# TIDA-01592_Power_Supply2.net
KiCad netlist of a schematic drawn in Altium Designer
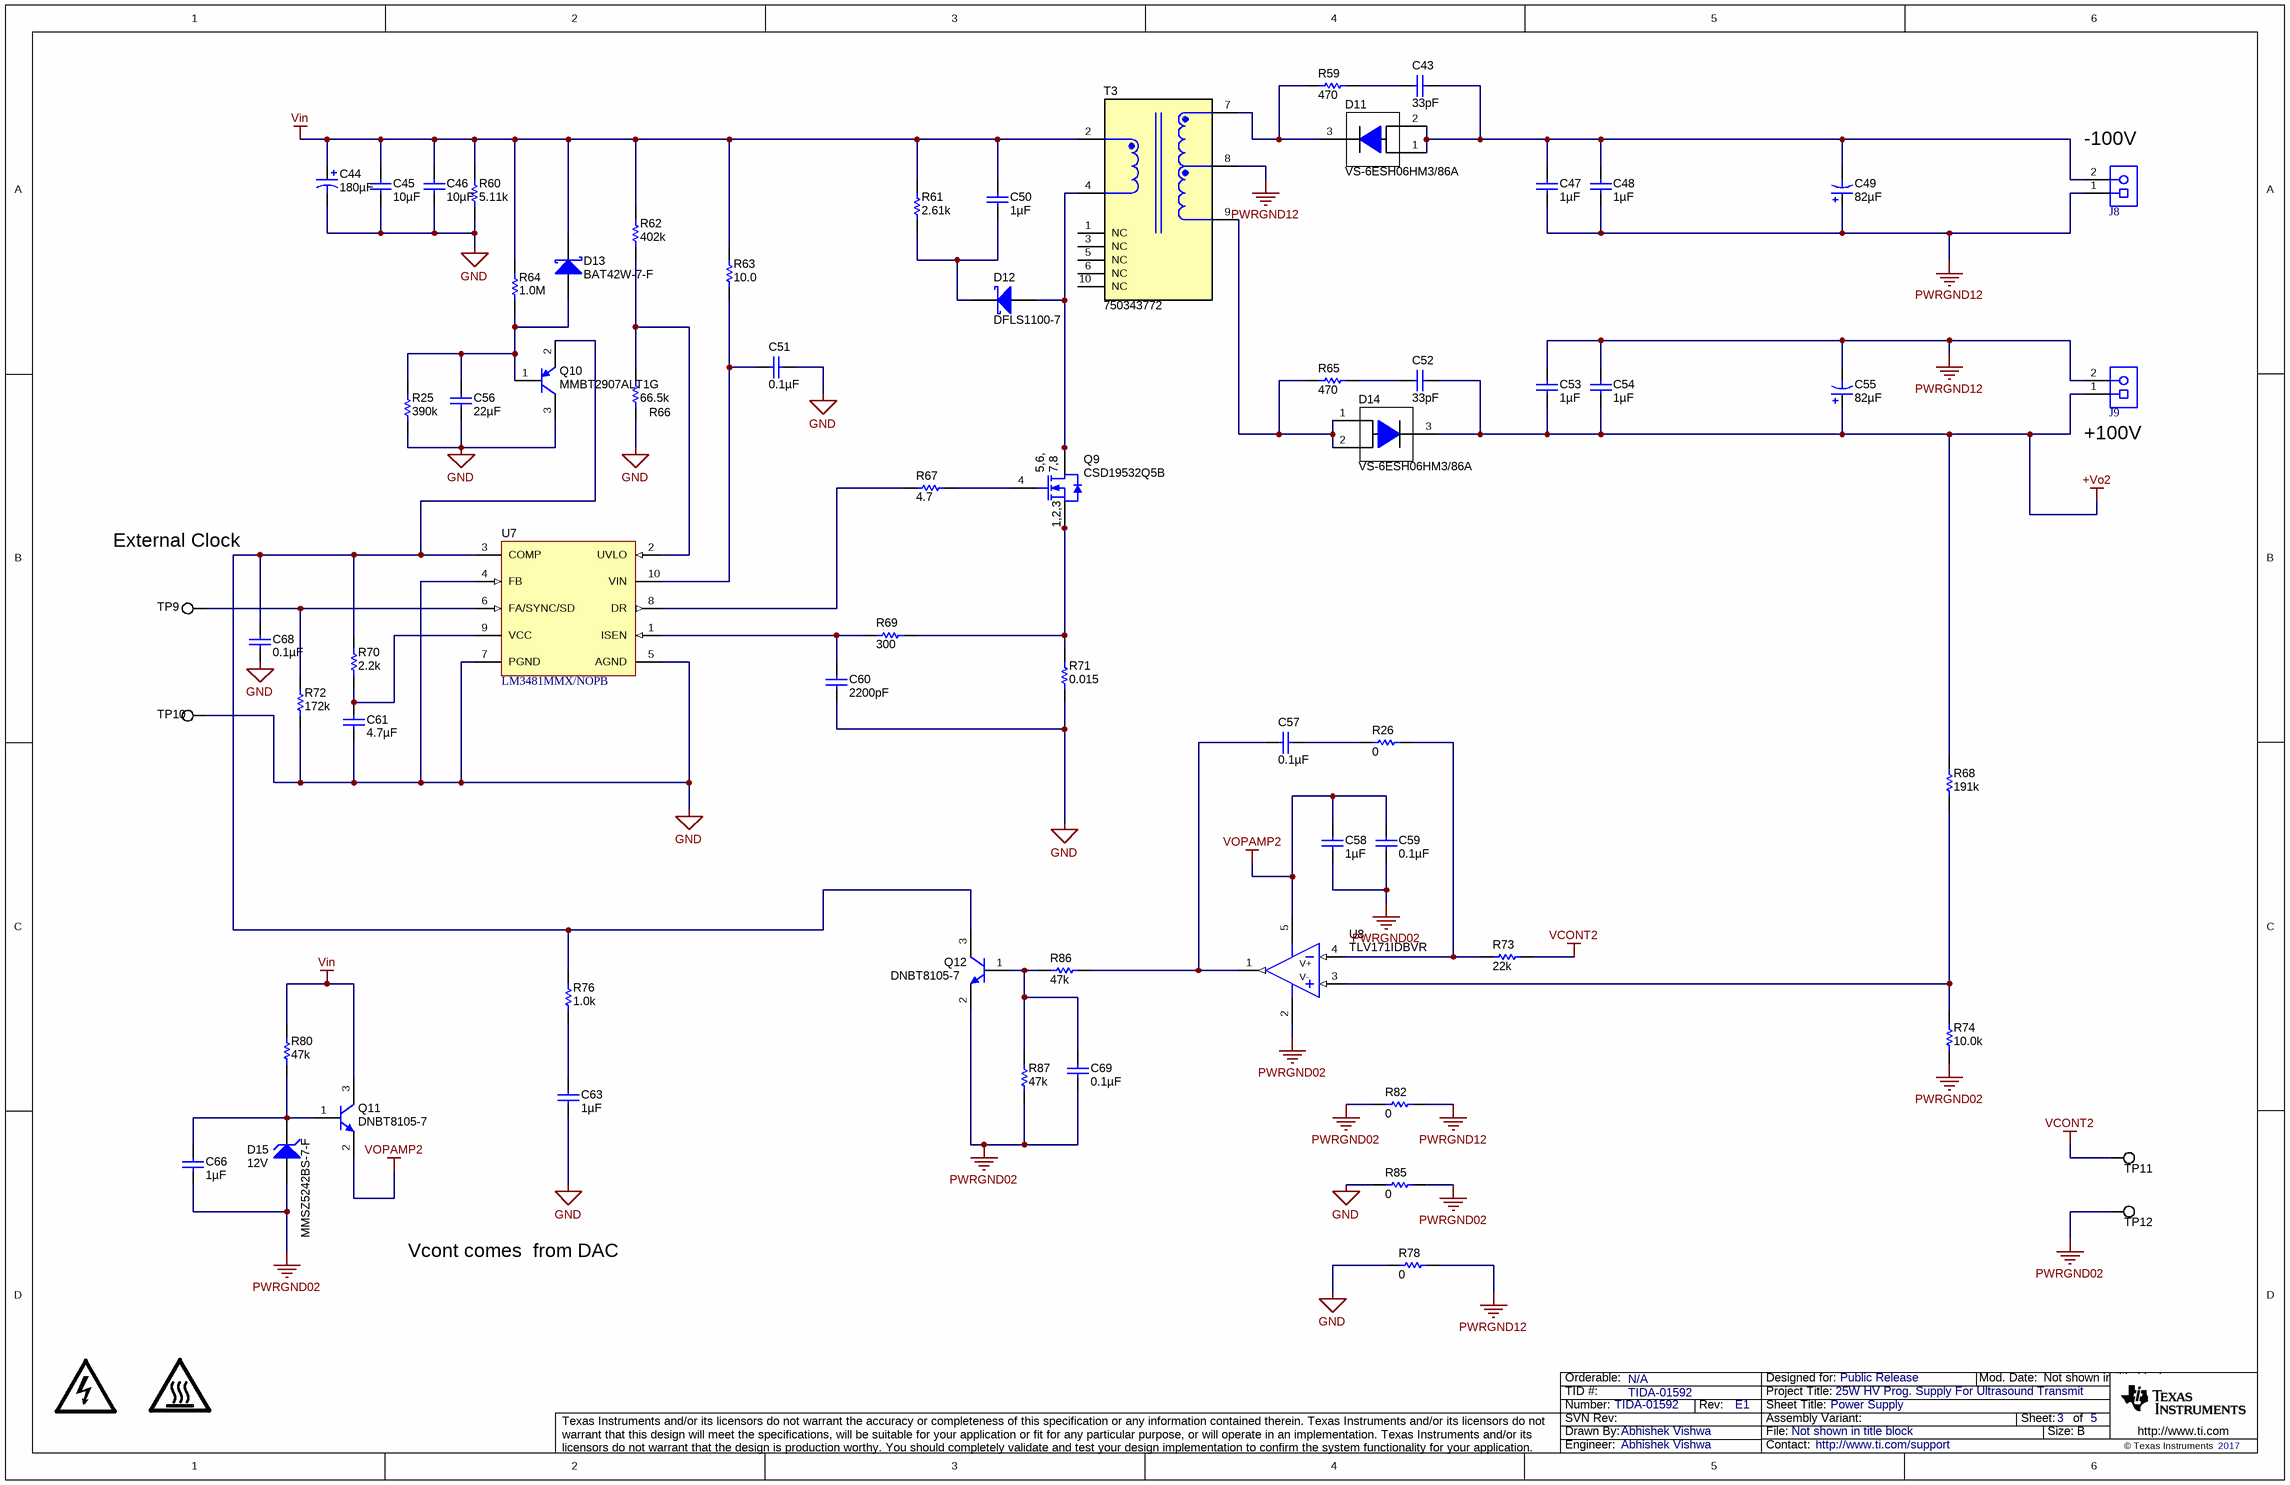
[diagram p0: TIDA-01592_Power Supply2.SchDoc]

(export (version "E")
  (design (tool "Eeschema 10.0.6"))
  (components
    (comp (ref "C43")
      (value "12067A330JAT2A")
      (footprint "1206")
      (description "CAP, CERM, 33 pF, 500 V,+/- 5%, C0G/NP0, 1206")
      (fields
        (field (name "VALUEDISPLAYED") "33pF")
        (field (name "MANUFACTURER") "AVX")
        (field (name "PUBLISHER") "Texas Instruments")
      )
      (libsource (lib "Capacitor_Ceramic") (part "12067A330JAT2A"))
    )
    (comp (ref "C44")
      (value "35TXW180MEFC6.3X25")
      (footprint "FC_630x1120")
      (description "CAP, AL, 180 µF, 35 V, +/- 20%, TH")
      (fields
        (field (name "VALUEDISPLAYED") "180µF")
        (field (name "MANUFACTURER") "Rubycon")
        (field (name "PUBLISHER") "Texas Instruments")
      )
      (libsource (lib "Capacitor_Aluminum") (part "EEU-FC1V470"))
    )
    (comp (ref "C45")
      (value "GRM31CR61H106KA12L")
      (footprint "1206_180")
      (description "CAP, CERM, 10 µF, 50 V,+/- 10%, X5R, 1206")
      (fields
        (field (name "VALUEDISPLAYED") "10µF")
        (field (name "MANUFACTURER") "MuRata")
        (field (name "PUBLISHER") "Texas Instruments")
      )
      (libsource (lib "Capacitor_Ceramic") (part "GRM31CR61H106KA12L"))
    )
    (comp (ref "C46")
      (value "GRM31CR61H106KA12L")
      (footprint "1206_180")
      (description "CAP, CERM, 10 µF, 50 V,+/- 10%, X5R, 1206")
      (fields
        (field (name "VALUEDISPLAYED") "10µF")
        (field (name "MANUFACTURER") "MuRata")
        (field (name "PUBLISHER") "Texas Instruments")
      )
      (libsource (lib "Capacitor_Ceramic") (part "GRM31CR61H106KA12L"))
    )
    (comp (ref "C47")
      (value "C4532X7T2E105M250KE")
      (footprint "1812_180")
      (description "CAP, CERM, 1 µF, 250 V,+/- 20%, X7T, 1812")
      (fields
        (field (name "VALUEDISPLAYED") "1µF")
        (field (name "MANUFACTURER") "TDK Corporation")
        (field (name "PUBLISHER") "Texas Instruments")
      )
      (libsource (lib "Capacitor_Ceramic") (part "C4532X7R1H105K160KA"))
    )
    (comp (ref "C48")
      (value "C4532X7T2E105M250KE")
      (footprint "1812_180")
      (description "CAP, CERM, 1 µF, 250 V,+/- 20%, X7T, 1812")
      (fields
        (field (name "VALUEDISPLAYED") "1µF")
        (field (name "MANUFACTURER") "TDK Corporation")
        (field (name "PUBLISHER") "Texas Instruments")
      )
      (libsource (lib "Capacitor_Ceramic") (part "C4532X7R1H105K160KA"))
    )
    (comp (ref "C49")
      (value "UCY2C820MPD9")
      (footprint "NHG_1000x2000")
      (description "CAP, AL, 82 µF, 160 V, +/- 20%, TH")
      (fields
        (field (name "VALUEDISPLAYED") "82µF")
        (field (name "MANUFACTURER") "Nichicon")
        (field (name "PUBLISHER") "Texas Instruments")
      )
      (libsource (lib "Capacitor_Aluminum") (part "ECA-2AHG101"))
    )
    (comp (ref "C50")
      (value "GRM31CR72A105KA01L")
      (footprint "1206_180")
      (description "CAP, CERM, 1 µF, 100 V,+/- 10%, X7R, 1206")
      (fields
        (field (name "VALUEDISPLAYED") "1µF")
        (field (name "MANUFACTURER") "MuRata")
        (field (name "PUBLISHER") "Texas Instruments")
      )
      (libsource (lib "Capacitor_Ceramic") (part "GRM31CR72A105KA01L"))
    )
    (comp (ref "C51")
      (value "GRM188R71H104KA93D")
      (footprint "0603")
      (description "CAP, CERM, 0.1 µF, 50 V,+/- 10%, X7R, 0603")
      (fields
        (field (name "VALUEDISPLAYED") "0.1µF")
        (field (name "MANUFACTURER") "MuRata")
        (field (name "PUBLISHER") "Texas Instruments")
      )
      (libsource (lib "Capacitor_Ceramic") (part "GRM188R71H104KA93D"))
    )
    (comp (ref "C52")
      (value "12067A330JAT2A")
      (footprint "1206")
      (description "CAP, CERM, 33 pF, 500 V,+/- 5%, C0G/NP0, 1206")
      (fields
        (field (name "VALUEDISPLAYED") "33pF")
        (field (name "MANUFACTURER") "AVX")
        (field (name "PUBLISHER") "Texas Instruments")
      )
      (libsource (lib "Capacitor_Ceramic") (part "12067A330JAT2A"))
    )
    (comp (ref "C53")
      (value "C4532X7T2E105M250KE")
      (footprint "1812_180")
      (description "CAP, CERM, 1 µF, 250 V,+/- 20%, X7T, 1812")
      (fields
        (field (name "VALUEDISPLAYED") "1µF")
        (field (name "MANUFACTURER") "TDK Corporation")
        (field (name "PUBLISHER") "Texas Instruments")
      )
      (libsource (lib "Capacitor_Ceramic") (part "C4532X7R1H105K160KA"))
    )
    (comp (ref "C54")
      (value "C4532X7T2E105M250KE")
      (footprint "1812_180")
      (description "CAP, CERM, 1 µF, 250 V,+/- 20%, X7T, 1812")
      (fields
        (field (name "VALUEDISPLAYED") "1µF")
        (field (name "MANUFACTURER") "TDK Corporation")
        (field (name "PUBLISHER") "Texas Instruments")
      )
      (libsource (lib "Capacitor_Ceramic") (part "C4532X7R1H105K160KA"))
    )
    (comp (ref "C55")
      (value "UCY2C820MPD9")
      (footprint "NHG_1000x2000")
      (description "CAP, AL, 82 µF, 160 V, +/- 20%, TH")
      (fields
        (field (name "VALUEDISPLAYED") "82µF")
        (field (name "MANUFACTURER") "Nichicon")
        (field (name "PUBLISHER") "Texas Instruments")
      )
      (libsource (lib "Capacitor_Aluminum") (part "ECA-2AHG101"))
    )
    (comp (ref "C56")
      (value "C2012X5R1V226M125AC")
      (footprint "0805_HV1")
      (description "CAP, CERM, 22 µF, 35 V,+/- 20%, X5R, 0805")
      (fields
        (field (name "VALUEDISPLAYED") "22µF")
        (field (name "MANUFACTURER") "TDK Corporation")
        (field (name "PUBLISHER") "Texas Instruments")
      )
      (libsource (lib "Capacitor_Ceramic") (part "GRM21BC81C226ME44L"))
    )
    (comp (ref "C57")
      (value "GRM188R71H104KA93D")
      (footprint "0603")
      (description "CAP, CERM, 0.1 µF, 50 V,+/- 10%, X7R, 0603")
      (fields
        (field (name "VALUEDISPLAYED") "0.1µF")
        (field (name "MANUFACTURER") "MuRata")
        (field (name "PUBLISHER") "Texas Instruments")
      )
      (libsource (lib "Capacitor_Ceramic") (part "GRM188R71H104KA93D"))
    )
    (comp (ref "C58")
      (value "UMK107AB7105KA-T")
      (footprint "0603")
      (description "CAP, CERM, 1 µF, 50 V,+/- 10%, X7R, 0603")
      (fields
        (field (name "VALUEDISPLAYED") "1µF")
        (field (name "MANUFACTURER") "Taiyo Yuden")
        (field (name "PUBLISHER") "Texas Instruments")
      )
      (libsource (lib "Capacitor_Ceramic") (part "UMK107AB7105KA-T"))
    )
    (comp (ref "C59")
      (value "GRM188R71H104KA93D")
      (footprint "0603")
      (description "CAP, CERM, 0.1 µF, 50 V,+/- 10%, X7R, 0603")
      (fields
        (field (name "VALUEDISPLAYED") "0.1µF")
        (field (name "MANUFACTURER") "MuRata")
        (field (name "PUBLISHER") "Texas Instruments")
      )
      (libsource (lib "Capacitor_Ceramic") (part "GRM188R71H104KA93D"))
    )
    (comp (ref "C60")
      (value "GRM155R61H222KA01D")
      (footprint "0402")
      (description "CAP, CERM, 2200 pF, 50 V,+/- 10%, X5R, 0402")
      (fields
        (field (name "VALUEDISPLAYED") "2200pF")
        (field (name "MANUFACTURER") "MuRata")
        (field (name "PUBLISHER") "Texas Instruments")
      )
      (libsource (lib "Capacitor_Ceramic") (part "GRM155R61H222KA01D"))
    )
    (comp (ref "C61")
      (value "0603ZD475KAT2A")
      (footprint "0603")
      (description "CAP, CERM, 4.7 µF, 10 V,+/- 10%, X5R, 0603")
      (fields
        (field (name "VALUEDISPLAYED") "4.7µF")
        (field (name "MANUFACTURER") "AVX")
        (field (name "PUBLISHER") "Texas Instruments")
      )
      (libsource (lib "Capacitor_Ceramic") (part "0603ZD475KAT2A"))
    )
    (comp (ref "C63")
      (value "C0603C105K3RACTU")
      (footprint "0603")
      (description "CAP, CERM, 1 µF, 25 V,+/- 10%, X7R, 0603")
      (fields
        (field (name "VALUEDISPLAYED") "1µF")
        (field (name "MANUFACTURER") "Kemet")
        (field (name "PUBLISHER") "Texas Instruments")
      )
      (libsource (lib "Capacitor_Ceramic") (part "C0603C105K3RACTU"))
    )
    (comp (ref "C66")
      (value "C0603C105K3RACTU")
      (footprint "0603")
      (description "CAP, CERM, 1 µF, 25 V,+/- 10%, X7R, 0603")
      (fields
        (field (name "VALUEDISPLAYED") "1µF")
        (field (name "MANUFACTURER") "Kemet")
        (field (name "PUBLISHER") "Texas Instruments")
      )
      (libsource (lib "Capacitor_Ceramic") (part "C0603C105K3RACTU"))
    )
    (comp (ref "C68")
      (value "GRM188R71H104KA93D")
      (footprint "0603")
      (description "CAP, CERM, 0.1 µF, 50 V,+/- 10%, X7R, 0603")
      (fields
        (field (name "VALUEDISPLAYED") "0.1µF")
        (field (name "MANUFACTURER") "MuRata")
        (field (name "PUBLISHER") "Texas Instruments")
      )
      (libsource (lib "Capacitor_Ceramic") (part "GRM188R71H104KA93D"))
    )
    (comp (ref "C69")
      (value "GRM188R71H104KA93D")
      (footprint "0603")
      (description "CAP, CERM, 0.1 µF, 50 V,+/- 10%, X7R, 0603")
      (fields
        (field (name "VALUEDISPLAYED") "0.1µF")
        (field (name "MANUFACTURER") "MuRata")
        (field (name "PUBLISHER") "Texas Instruments")
      )
      (libsource (lib "Capacitor_Ceramic") (part "GRM188R71H104KA93D"))
    )
    (comp (ref "D11")
      (value "VS-6ESH06HM3/86A")
      (footprint "TO-277A")
      (description "Diode, Hyperfast, 600 V, 6 A, AEC-Q101, TO-277A")
      (fields
        (field (name "MANUFACTURER") "Vishay-Semiconductor")
        (field (name "SYMBOLCREATOR") "a0412235")
        (field (name "PUBLISHER") "Texas Instruments")
      )
      (libsource (lib "Diode") (part "VS-6ESH06HM3/86A"))
    )
    (comp (ref "D12")
      (value "DFLS1100-7")
      (footprint "PowerDI123")
      (description "Diode, Schottky, 100 V, 1 A, PowerDI123")
      (fields (field (name "MANUFACTURER") "Diodes Inc.") (field (name "PUBLISHER") "Texas Instruments"))
      (libsource (lib "Diode") (part "DFLS1100-7"))
    )
    (comp (ref "D13")
      (value "BAT42W-7-F")
      (footprint "SOD-123")
      (description "Diode, Schottky, 30 V, 0.2 A, SOD-123")
      (fields (field (name "MANUFACTURER") "Diodes Inc.") (field (name "PUBLISHER") "Texas Instruments"))
      (libsource (lib "Diode") (part "BAT42W-7-F"))
    )
    (comp (ref "D14")
      (value "VS-6ESH06HM3/86A")
      (footprint "TO-277A")
      (description "Diode, Hyperfast, 600 V, 6 A, AEC-Q101, TO-277A")
      (fields
        (field (name "MANUFACTURER") "Vishay-Semiconductor")
        (field (name "SYMBOLCREATOR") "a0412235")
        (field (name "PUBLISHER") "Texas Instruments")
      )
      (libsource (lib "") (part "VS-6ESH06HM3/86A_1"))
    )
    (comp (ref "D15")
      (value "MMSZ5242BS-7-F")
      (footprint "SOD-323")
      (description "Diode, Zener, 12 V, 200 mW, SOD-323")
      (fields
        (field (name "ALTIUM_VALUE") "12V")
        (field (name "MANUFACTURER") "Diodes Inc.")
        (field (name "SYMBOLCREATOR") "a0412235")
        (field (name "PUBLISHER") "Texas Instruments")
      )
      (libsource (lib "ZenerDiodes") (part "MMSZ5242BS-7-F"))
    )
    (comp (ref "J8")
      (value "1727010")
      (footprint "PhoenixConact_1727010")
      (description "Conn Term Block, 2POS, 3.81mm, TH")
      (fields
        (field (name "MANUFACTURER") "Phoenix Contact")
        (field (name "SYMBOLCREATOR") "a0412235")
        (field (name "PUBLISHER") "Texas Instruments")
      )
      (libsource (lib "Connectors_Phoenix_Contact") (part "1727010"))
    )
    (comp (ref "J9")
      (value "1727010")
      (footprint "PhoenixConact_1727010")
      (description "Conn Term Block, 2POS, 3.81mm, TH")
      (fields
        (field (name "MANUFACTURER") "Phoenix Contact")
        (field (name "SYMBOLCREATOR") "a0412235")
        (field (name "PUBLISHER") "Texas Instruments")
      )
      (libsource (lib "Connectors_Phoenix_Contact") (part "1727010"))
    )
    (comp (ref "Q9")
      (value "CSD19532Q5B")
      (footprint "DNK0008A")
      (description "MOSFET, N-CH, 100 V, 17 A, DNK0008A (VSON-CLIP-8)")
      (fields
        (field (name "MANUFACTURER") "Texas Instruments")
        (field (name "PUBLISHER") "Texas Instruments")
      )
      (libsource (lib "FETs") (part "CSD19532Q5B"))
    )
    (comp (ref "Q10")
      (value "MMBT2907ALT1G")
      (footprint "SOT-23")
      (description "Transistor, PNP, 60 V, 0.6 A, SOT-23")
      (fields (field (name "MANUFACTURER") "ON Semiconductor") (field (name "PUBLISHER") "Texas Instruments"))
      (libsource (lib "Bipolar_Transistor") (part "MMBT2907ALT1G, ON Semiconductor"))
    )
    (comp (ref "Q11")
      (value "DNBT8105-7")
      (footprint "SOT-23")
      (description "Transistor, NPN, 60 V, 1 A, AEC-Q101, SOT-23")
      (fields (field (name "MANUFACTURER") "Diodes Inc.") (field (name "PUBLISHER") "Texas Instruments"))
      (libsource (lib "Bipolar_Transistor") (part "DNBT8105-7, Diodes Inc."))
    )
    (comp (ref "Q12")
      (value "DNBT8105-7")
      (footprint "SOT-23")
      (description "Transistor, NPN, 60 V, 1 A, AEC-Q101, SOT-23")
      (fields (field (name "MANUFACTURER") "Diodes Inc.") (field (name "PUBLISHER") "Texas Instruments"))
      (libsource (lib "Bipolar_Transistor") (part "DNBT8105-7, Diodes Inc."))
    )
    (comp (ref "R25")
      (value "CRCW0603390KJNEA")
      (footprint "0603")
      (description "RES, 390 k, 5%, 0.1 W, 0603")
      (fields
        (field (name "VALUEDISPLAYED") "390k")
        (field (name "MANUFACTURER") "Vishay-Dale")
        (field (name "PUBLISHER") "Texas Instruments")
      )
      (libsource (lib "Resistor_0603") (part "CRCW0603390KJNEA"))
    )
    (comp (ref "R26")
      (value "CRCW04020000Z0ED")
      (footprint "0402")
      (description "RES, 0, 5%, 0.063 W, 0402")
      (fields
        (field (name "VALUEDISPLAYED") "0")
        (field (name "MANUFACTURER") "Vishay-Dale")
        (field (name "PUBLISHER") "Texas Instruments")
      )
      (libsource (lib "Resistor_0402") (part "CRCW04020000Z0ED"))
    )
    (comp (ref "R59")
      (value "CRCW1206470RJNEA")
      (footprint "1206")
      (description "RES, 470, 5%, 0.25 W, 1206")
      (fields
        (field (name "VALUEDISPLAYED") "470")
        (field (name "MANUFACTURER") "Vishay-Dale")
        (field (name "PUBLISHER") "Texas Instruments")
      )
      (libsource (lib "Resistor_1206") (part "CRCW1206470RJNEA"))
    )
    (comp (ref "R60")
      (value "TNPW06035K11BEEA")
      (footprint "TNPW0603")
      (description "RES, 5.11 k, 0.1%, 0.1 W, AEC-Q200 Grade 1, 0603")
      (fields
        (field (name "VALUEDISPLAYED") "5.11k")
        (field (name "MANUFACTURER") "Vishay-Dale")
        (field (name "PUBLISHER") "Texas Instruments")
      )
      (libsource (lib "Resistor_0603") (part "TNPW06035K11BEEA"))
    )
    (comp (ref "R61")
      (value "CRCW20102K61FKEF")
      (footprint "2010")
      (description "RES, 2.61 k, 1%, 0.75 W, AEC-Q200 Grade 0, 2010")
      (fields
        (field (name "VALUEDISPLAYED") "2.61k")
        (field (name "MANUFACTURER") "Vishay-Dale")
        (field (name "PUBLISHER") "Texas Instruments")
      )
      (libsource (lib "Resistor_2010") (part "CRCW20102K61FKEF"))
    )
    (comp (ref "R62")
      (value "CRCW0603402KFKEA")
      (footprint "0603")
      (description "RES, 402 k, 1%, 0.1 W, 0603")
      (fields
        (field (name "VALUEDISPLAYED") "402k")
        (field (name "MANUFACTURER") "Vishay-Dale")
        (field (name "PUBLISHER") "Texas Instruments")
      )
      (libsource (lib "Resistor_0603") (part "CRCW0603402KFKEA"))
    )
    (comp (ref "R63")
      (value "CRCW060310R0FKEAHP")
      (footprint "0603")
      (description "RES, 10.0, 1%, 0.25 W, 0603")
      (fields
        (field (name "R4") "10.0")
        (field (name "MANUFACTURER") "Vishay-Dale")
        (field (name "PUBLISHER") "Texas Instruments")
      )
      (libsource (lib "Resistor_0603") (part "CRCW060310R0FKEAHP"))
    )
    (comp (ref "R64")
      (value "CRCW06031M00JNEA")
      (footprint "0603")
      (description "RES, 1.0 M, 5%, 0.1 W, 0603")
      (fields
        (field (name "VALUEDISPLAYED") "1.0M")
        (field (name "MANUFACTURER") "Vishay-Dale")
        (field (name "PUBLISHER") "Texas Instruments")
      )
      (libsource (lib "Resistor_0603") (part "CRCW06031M00JNEA"))
    )
    (comp (ref "R65")
      (value "CRCW1206470RJNEA")
      (footprint "1206")
      (description "RES, 470, 5%, 0.25 W, 1206")
      (fields
        (field (name "VALUEDISPLAYED") "470")
        (field (name "MANUFACTURER") "Vishay-Dale")
        (field (name "PUBLISHER") "Texas Instruments")
      )
      (libsource (lib "Resistor_1206") (part "CRCW1206470RJNEA"))
    )
    (comp (ref "R66")
      (value "CRCW060366K5FKEA")
      (footprint "0603")
      (description "RES, 66.5 k, 1%, 0.1 W, 0603")
      (fields
        (field (name "VALUEDISPLAYED") "66.5k")
        (field (name "MANUFACTURER") "Vishay-Dale")
        (field (name "PUBLISHER") "Texas Instruments")
      )
      (libsource (lib "Resistor_0603") (part "CRCW060366K5FKEA"))
    )
    (comp (ref "R67")
      (value "CRCW06034R70JNEA")
      (footprint "0603")
      (description "RES, 4.7, 5%, 0.1 W, 0603")
      (fields
        (field (name "VALUEDISPLAYED") "4.7")
        (field (name "MANUFACTURER") "Vishay-Dale")
        (field (name "PUBLISHER") "Texas Instruments")
      )
      (libsource (lib "Resistor_0603") (part "CRCW06034R70JNEA"))
    )
    (comp (ref "R68")
      (value "CRCW0603191KFKEA")
      (footprint "0603")
      (description "RES, 191 k, 1%, 0.1 W, 0603")
      (fields
        (field (name "VALUEDISPLAYED") "191k")
        (field (name "MANUFACTURER") "Vishay-Dale")
        (field (name "PUBLISHER") "Texas Instruments")
      )
      (libsource (lib "Resistor_0603") (part "CRCW0603191KFKEA"))
    )
    (comp (ref "R69")
      (value "CRCW0603300RJNEA")
      (footprint "0603")
      (description "RES, 300, 5%, 0.1 W, 0603")
      (fields
        (field (name "VALUEDISPLAYED") "300")
        (field (name "MANUFACTURER") "Vishay-Dale")
        (field (name "PUBLISHER") "Texas Instruments")
      )
      (libsource (lib "Resistor_0603") (part "CRCW0603300RJNEA"))
    )
    (comp (ref "R70")
      (value "ERJ-3GEYJ222V")
      (footprint "0603")
      (description "RES, 2.2 k, 5%, 0.1 W, AEC-Q200 Grade 0, 0603")
      (fields
        (field (name "VALUEDISPLAYED") "2.2k")
        (field (name "MANUFACTURER") "Panasonic")
        (field (name "PUBLISHER") "Texas Instruments")
      )
      (libsource (lib "Resistor_0603") (part "ERJ-3GEYJ222V"))
    )
    (comp (ref "R71")
      (value "WSL2010R0150FEA18")
      (footprint "2010")
      (description "RES, 0.015, 1%, 1 W, 2010")
      (fields
        (field (name "VALUEDISPLAYED") "0.015")
        (field (name "MANUFACTURER") "Vishay-Dale")
        (field (name "PUBLISHER") "Texas Instruments")
      )
      (libsource (lib "Resistor_2010") (part "WSL2010R0150FEA18"))
    )
    (comp (ref "R72")
      (value "RT0603DRE07172KL")
      (footprint "0603")
      (description "RES, 172 k, 0.5%, 0.1 W, 0603")
      (fields
        (field (name "VALUEDISPLAYED") "172k")
        (field (name "MANUFACTURER") "Yageo America")
        (field (name "PUBLISHER") "Texas Instruments")
      )
      (libsource (lib "Resistor_0603") (part "RT0603DRE07172KL"))
    )
    (comp (ref "R73")
      (value "CRCW060322K0JNEA")
      (footprint "0603")
      (description "RES, 22 k, 5%, 0.1 W, 0603")
      (fields
        (field (name "VALUEDISPLAYED") "22k")
        (field (name "MANUFACTURER") "Vishay-Dale")
        (field (name "PUBLISHER") "Texas Instruments")
      )
      (libsource (lib "Resistor_0603") (part "CRCW060322K0JNEA"))
    )
    (comp (ref "R74")
      (value "CRCW060310K0FKEA")
      (footprint "0603")
      (description "RES, 10.0 k, 1%, 0.1 W, 0603")
      (fields
        (field (name "VALUEDISPLAYED") "10.0k")
        (field (name "MANUFACTURER") "Vishay-Dale")
        (field (name "PUBLISHER") "Texas Instruments")
      )
      (libsource (lib "Resistor_0603") (part "CRCW060310K0FKEA"))
    )
    (comp (ref "R76")
      (value "CRCW06031K00JNEA")
      (footprint "0603")
      (description "RES, 1.0 k, 5%, 0.1 W, 0603")
      (fields
        (field (name "VALUEDISPLAYED") "1.0k")
        (field (name "MANUFACTURER") "Vishay-Dale")
        (field (name "PUBLISHER") "Texas Instruments")
      )
      (libsource (lib "Resistor_0603") (part "CRCW06031K00JNEA"))
    )
    (comp (ref "R78")
      (value "CRCW20100000Z0EF")
      (footprint "2010L")
      (description "RES, 0, 5%, 0.75 W, AEC-Q200 Grade 0, 2010")
      (fields
        (field (name "VALUEDISPLAYED") "0")
        (field (name "MANUFACTURER") "Vishay-Dale")
        (field (name "PUBLISHER") "Texas Instruments")
      )
      (libsource (lib "Resistor_2010") (part "CRCW20100000Z0EF"))
    )
    (comp (ref "R80")
      (value "CRCW120647K0JNEA")
      (footprint "1206")
      (description "RES, 47 k, 5%, 0.25 W, 1206")
      (fields
        (field (name "VALUEDISPLAYED") "47k")
        (field (name "MANUFACTURER") "Vishay-Dale")
        (field (name "PUBLISHER") "Texas Instruments")
      )
      (libsource (lib "Resistor_1206") (part "CRCW120647K0JNEA"))
    )
    (comp (ref "R82")
      (value "CRCW20100000Z0EF")
      (footprint "2010L")
      (description "RES, 0, 5%, 0.75 W, AEC-Q200 Grade 0, 2010")
      (fields
        (field (name "VALUEDISPLAYED") "0")
        (field (name "MANUFACTURER") "Vishay-Dale")
        (field (name "PUBLISHER") "Texas Instruments")
      )
      (libsource (lib "Resistor_2010") (part "CRCW20100000Z0EF"))
    )
    (comp (ref "R85")
      (value "CRCW20100000Z0EF")
      (footprint "2010L")
      (description "RES, 0, 5%, 0.75 W, AEC-Q200 Grade 0, 2010")
      (fields
        (field (name "VALUEDISPLAYED") "0")
        (field (name "MANUFACTURER") "Vishay-Dale")
        (field (name "PUBLISHER") "Texas Instruments")
      )
      (libsource (lib "Resistor_2010") (part "CRCW20100000Z0EF"))
    )
    (comp (ref "R86")
      (value "RC0603JR-0747KL")
      (footprint "0603")
      (description "RES, 47 k, 5%, 0.1 W, 0603")
      (fields
        (field (name "VALUEDISPLAYED") "47k")
        (field (name "MANUFACTURER") "Yageo America")
        (field (name "PUBLISHER") "Texas Instruments")
      )
      (libsource (lib "Resistor_0603") (part "RC0603JR-0747KL"))
    )
    (comp (ref "R87")
      (value "RC0603JR-0747KL")
      (footprint "0603")
      (description "RES, 47 k, 5%, 0.1 W, 0603")
      (fields
        (field (name "VALUEDISPLAYED") "47k")
        (field (name "MANUFACTURER") "Yageo America")
        (field (name "PUBLISHER") "Texas Instruments")
      )
      (libsource (lib "Resistor_0603") (part "RC0603JR-0747KL"))
    )
    (comp (ref "T3")
      (value "750343772")
      (footprint "Wurth_EE16_7_5_5278")
      (description "Transformer, 13 uH, TH")
      (fields (field (name "MANUFACTURER") "Wurth Elektronik"))
      (libsource (lib "Altium Vault - TI") (part "Wurth_750343772"))
    )
    (comp (ref "TP9")
      (value "5002")
      (footprint "Keystone5002")
      (description "Test Point, Miniature, White, TH")
      (fields (field (name "MANUFACTURER") "Keystone") (field (name "PUBLISHER") "Texas Instruments"))
      (libsource (lib "Connectors_Keystone") (part "5002"))
    )
    (comp (ref "TP10")
      (value "5002")
      (footprint "Keystone5002")
      (description "Test Point, Miniature, White, TH")
      (fields (field (name "MANUFACTURER") "Keystone") (field (name "PUBLISHER") "Texas Instruments"))
      (libsource (lib "Connectors_Keystone") (part "5002"))
    )
    (comp (ref "TP11")
      (value "5002")
      (footprint "Keystone5002")
      (description "Test Point, Miniature, White, TH")
      (fields (field (name "MANUFACTURER") "Keystone") (field (name "PUBLISHER") "Texas Instruments"))
      (libsource (lib "Connectors_Keystone") (part "5002"))
    )
    (comp (ref "TP12")
      (value "5002")
      (footprint "Keystone5002")
      (description "Test Point, Miniature, White, TH")
      (fields (field (name "MANUFACTURER") "Keystone") (field (name "PUBLISHER") "Texas Instruments"))
      (libsource (lib "Connectors_Keystone") (part "5002"))
    )
    (comp (ref "U7")
      (value "LM3481MMX/NOPB")
      (footprint "MUB10A_N")
      (description "High Efficiency Low-Side N-Channel Controller for Switching Regulators, 10-pin MSOP, Pb-Free")
      (fields (field (name "MANUFACTURER") "Texas Instruments") (field (name "PUBLISHER") "Altium Limited"))
      (libsource (lib "NSC MiscPower") (part "LM3481MMX/NOPB"))
    )
    (comp (ref "U8")
      (value "TLV171IDBVR")
      (footprint "DBV0005A_N")
      (description "36V, Low-Power, RRO, General-Purpose Operational Amplifier, DBV0005A (SOT-23-5)")
      (fields
        (field (name "ALTERNATE PARTNUMBER") "TLV171IDBVT")
        (field (name "MANUFACTURER") "Texas Instruments")
        (field (name "PUBLISHER") "Texas Instruments")
      )
      (libsource (lib "TI_Pre_Release1") (part "TLV171IDBVR"))
    )
  )
  (nets
    (net (code "1") (name "+Vo2") (class "Default")
      (node (ref "C52") (pin "1") (pinfunction "1_1") (pintype "passive"))
      (node (ref "C53") (pin "2") (pinfunction "2_2") (pintype "passive"))
      (node (ref "C54") (pin "2") (pinfunction "2_2") (pintype "passive"))
      (node (ref "C55") (pin "1") (pinfunction "+_1") (pintype "passive"))
      (node (ref "D14") (pin "3") (pinfunction "K_3") (pintype "passive"))
      (node (ref "J9") (pin "1") (pinfunction "1_1") (pintype "passive"))
      (node (ref "R68") (pin "2") (pinfunction "2_2") (pintype "passive"))
    )
    (net (code "2") (name "GND") (class "Default")
      (node (ref "C44") (pin "2") (pinfunction "-_2") (pintype "passive"))
      (node (ref "C45") (pin "2") (pinfunction "2_2") (pintype "passive"))
      (node (ref "C46") (pin "2") (pinfunction "2_2") (pintype "passive"))
      (node (ref "C51") (pin "1") (pinfunction "1_1") (pintype "passive"))
      (node (ref "C56") (pin "2") (pinfunction "2_2") (pintype "passive"))
      (node (ref "C60") (pin "2") (pinfunction "2_2") (pintype "passive"))
      (node (ref "C61") (pin "2") (pinfunction "2_2") (pintype "passive"))
      (node (ref "C63") (pin "2") (pinfunction "2_2") (pintype "passive"))
      (node (ref "C68") (pin "1") (pinfunction "1_1") (pintype "passive"))
      (node (ref "Q10") (pin "3") (pinfunction "C_3") (pintype "passive"))
      (node (ref "R25") (pin "1") (pinfunction "1_1") (pintype "passive"))
      (node (ref "R60") (pin "1") (pinfunction "1_1") (pintype "passive"))
      (node (ref "R66") (pin "1") (pinfunction "1_1") (pintype "passive"))
      (node (ref "R71") (pin "1") (pinfunction "1_1") (pintype "passive"))
      (node (ref "R72") (pin "1") (pinfunction "1_1") (pintype "passive"))
      (node (ref "R78") (pin "1") (pinfunction "1_1") (pintype "passive"))
      (node (ref "R85") (pin "1") (pinfunction "1_1") (pintype "passive"))
      (node (ref "TP10") (pin "1") (pintype "passive"))
      (node (ref "U7") (pin "4") (pinfunction "FB_4") (pintype "input"))
      (node (ref "U7") (pin "5") (pinfunction "AGND_5") (pintype "power_in"))
      (node (ref "U7") (pin "7") (pinfunction "PGND_7") (pintype "power_in"))
    )
    (net (code "3") (name "Net-(C43-Pad2)") (class "Default")
      (node (ref "C43") (pin "2") (pinfunction "2_2") (pintype "passive"))
      (node (ref "R59") (pin "2") (pinfunction "2_2") (pintype "passive"))
    )
    (net (code "4") (name "Net-(C49--)") (class "Default")
      (node (ref "C43") (pin "1") (pinfunction "1_1") (pintype "passive"))
      (node (ref "C47") (pin "1") (pinfunction "1_1") (pintype "passive"))
      (node (ref "C48") (pin "1") (pinfunction "1_1") (pintype "passive"))
      (node (ref "C49") (pin "2") (pinfunction "-_2") (pintype "passive"))
      (node (ref "D11") (pin "1") (pinfunction "A_1") (pintype "passive"))
      (node (ref "D11") (pin "2") (pinfunction "A_2") (pintype "passive"))
      (node (ref "J8") (pin "2") (pinfunction "2_2") (pintype "passive"))
    )
    (net (code "5") (name "Net-(C52-Pad2)") (class "Default")
      (node (ref "C52") (pin "2") (pinfunction "2_2") (pintype "passive"))
      (node (ref "R65") (pin "2") (pinfunction "2_2") (pintype "passive"))
    )
    (net (code "6") (name "Net-(C57-Pad2)") (class "Default")
      (node (ref "C57") (pin "2") (pinfunction "2_2") (pintype "passive"))
      (node (ref "R26") (pin "1") (pinfunction "1_1") (pintype "passive"))
    )
    (net (code "7") (name "Net-(C63-Pad1)") (class "Default")
      (node (ref "C63") (pin "1") (pinfunction "1_1") (pintype "passive"))
      (node (ref "R76") (pin "1") (pinfunction "1_1") (pintype "passive"))
    )
    (net (code "8") (name "Net-(D11-K)") (class "Default")
      (node (ref "D11") (pin "3") (pinfunction "K_3") (pintype "passive"))
      (node (ref "R59") (pin "1") (pinfunction "1_1") (pintype "passive"))
      (node (ref "T3") (pin "7") (pinfunction "7_7") (pintype "passive"))
    )
    (net (code "9") (name "Net-(D12-A)") (class "Default")
      (node (ref "D12") (pin "2") (pinfunction "A_2") (pintype "passive"))
      (node (ref "Q9") (pin "5") (pinfunction "D_5") (pintype "passive"))
      (node (ref "Q9") (pin "6") (pinfunction "D_6") (pintype "passive"))
      (node (ref "Q9") (pin "7") (pinfunction "D_7") (pintype "passive"))
      (node (ref "Q9") (pin "8") (pinfunction "D_8") (pintype "passive"))
      (node (ref "Q9") (pin "9") (pinfunction "D_9") (pintype "passive"))
      (node (ref "T3") (pin "4") (pinfunction "4_4") (pintype "passive"))
    )
    (net (code "10") (name "Net-(D12-K)") (class "Default")
      (node (ref "C50") (pin "2") (pinfunction "2_2") (pintype "passive"))
      (node (ref "D12") (pin "1") (pinfunction "K_1") (pintype "passive"))
      (node (ref "R61") (pin "1") (pinfunction "1_1") (pintype "passive"))
    )
    (net (code "11") (name "Net-(D13-A)") (class "Default")
      (node (ref "C56") (pin "1") (pinfunction "1_1") (pintype "passive"))
      (node (ref "D13") (pin "2") (pinfunction "A_2") (pintype "passive"))
      (node (ref "Q10") (pin "1") (pinfunction "B_1") (pintype "passive"))
      (node (ref "R25") (pin "2") (pinfunction "2_2") (pintype "passive"))
      (node (ref "R64") (pin "1") (pinfunction "1_1") (pintype "passive"))
    )
    (net (code "12") (name "Net-(D14-A-Pad1)") (class "Default")
      (node (ref "D14") (pin "1") (pinfunction "A_1") (pintype "passive"))
      (node (ref "D14") (pin "2") (pinfunction "A_2") (pintype "passive"))
      (node (ref "R65") (pin "1") (pinfunction "1_1") (pintype "passive"))
      (node (ref "T3") (pin "9") (pinfunction "9_9") (pintype "passive"))
    )
    (net (code "13") (name "Net-(D15-K)") (class "Default")
      (node (ref "C66") (pin "1") (pinfunction "1_1") (pintype "passive"))
      (node (ref "D15") (pin "1") (pinfunction "K_1") (pintype "passive"))
      (node (ref "Q11") (pin "1") (pinfunction "B_1") (pintype "passive"))
      (node (ref "R80") (pin "1") (pinfunction "1_1") (pintype "passive"))
    )
    (net (code "14") (name "Net-(Q9-G)") (class "Default")
      (node (ref "Q9") (pin "4") (pinfunction "G_4") (pintype "passive"))
      (node (ref "R67") (pin "2") (pinfunction "2_2") (pintype "passive"))
    )
    (net (code "15") (name "Net-(Q9-S-Pad1)") (class "Default")
      (node (ref "Q9") (pin "1") (pinfunction "S_1") (pintype "passive"))
      (node (ref "Q9") (pin "2") (pinfunction "S_2") (pintype "passive"))
      (node (ref "Q9") (pin "3") (pinfunction "S_3") (pintype "passive"))
      (node (ref "R69") (pin "2") (pinfunction "2_2") (pintype "passive"))
      (node (ref "R71") (pin "2") (pinfunction "2_2") (pintype "passive"))
    )
    (net (code "16") (name "Net-(Q10-E)") (class "Default")
      (node (ref "C68") (pin "2") (pinfunction "2_2") (pintype "passive"))
      (node (ref "Q10") (pin "2") (pinfunction "E_2") (pintype "passive"))
      (node (ref "Q12") (pin "3") (pinfunction "C_3") (pintype "passive"))
      (node (ref "R70") (pin "1") (pinfunction "1_1") (pintype "passive"))
      (node (ref "R76") (pin "2") (pinfunction "2_2") (pintype "passive"))
      (node (ref "U7") (pin "3") (pinfunction "COMP_3") (pintype "passive"))
    )
    (net (code "17") (name "Net-(Q12-B)") (class "Default")
      (node (ref "C69") (pin "2") (pinfunction "2_2") (pintype "passive"))
      (node (ref "Q12") (pin "1") (pinfunction "B_1") (pintype "passive"))
      (node (ref "R86") (pin "2") (pinfunction "2_2") (pintype "passive"))
      (node (ref "R87") (pin "1") (pinfunction "1_1") (pintype "passive"))
    )
    (net (code "18") (name "Net-(U7-DR)") (class "Default")
      (node (ref "R67") (pin "1") (pinfunction "1_1") (pintype "passive"))
      (node (ref "U7") (pin "8") (pinfunction "DR_8") (pintype "output"))
    )
    (net (code "19") (name "Net-(U7-FA{slash}SYNC{slash}SD)") (class "Default")
      (node (ref "R72") (pin "2") (pinfunction "2_2") (pintype "passive"))
      (node (ref "TP9") (pin "1") (pintype "passive"))
      (node (ref "U7") (pin "6") (pinfunction "FA/SYNC/SD_6") (pintype "input"))
    )
    (net (code "20") (name "Net-(U7-ISEN)") (class "Default")
      (node (ref "C60") (pin "1") (pinfunction "1_1") (pintype "passive"))
      (node (ref "R69") (pin "1") (pinfunction "1_1") (pintype "passive"))
      (node (ref "U7") (pin "1") (pinfunction "ISEN_1") (pintype "input"))
    )
    (net (code "21") (name "Net-(U7-UVLO)") (class "Default")
      (node (ref "R62") (pin "1") (pinfunction "1_1") (pintype "passive"))
      (node (ref "R66") (pin "2") (pinfunction "2_2") (pintype "passive"))
      (node (ref "U7") (pin "2") (pinfunction "UVLO_2") (pintype "input"))
    )
    (net (code "22") (name "Net-(U7-VCC)") (class "Default")
      (node (ref "C61") (pin "1") (pinfunction "1_1") (pintype "passive"))
      (node (ref "R70") (pin "2") (pinfunction "2_2") (pintype "passive"))
      (node (ref "U7") (pin "9") (pinfunction "VCC_9") (pintype "power_in"))
    )
    (net (code "23") (name "Net-(U7-VIN)") (class "Default")
      (node (ref "C51") (pin "2") (pinfunction "2_2") (pintype "passive"))
      (node (ref "R63") (pin "2") (pinfunction "2_2") (pintype "passive"))
      (node (ref "U7") (pin "10") (pinfunction "VIN_10") (pintype "power_in"))
    )
    (net (code "24") (name "Net-(U8-IN+)") (class "Default")
      (node (ref "R68") (pin "1") (pinfunction "1_1") (pintype "passive"))
      (node (ref "R74") (pin "1") (pinfunction "1_1") (pintype "passive"))
      (node (ref "U8") (pin "3") (pinfunction "IN+_3") (pintype "input"))
    )
    (net (code "25") (name "Net-(U8-IN-)") (class "Default")
      (node (ref "R26") (pin "2") (pinfunction "2_2") (pintype "passive"))
      (node (ref "R73") (pin "1") (pinfunction "1_1") (pintype "passive"))
      (node (ref "U8") (pin "4") (pinfunction "IN-_4") (pintype "input"))
    )
    (net (code "26") (name "Net-(U8-OUT)") (class "Default")
      (node (ref "C57") (pin "1") (pinfunction "1_1") (pintype "passive"))
      (node (ref "R86") (pin "1") (pinfunction "1_1") (pintype "passive"))
      (node (ref "U8") (pin "1") (pinfunction "OUT_1") (pintype "output"))
    )
    (net (code "27") (name "PWRGND02") (class "Default")
      (node (ref "C58") (pin "2") (pinfunction "2_2") (pintype "passive"))
      (node (ref "C59") (pin "2") (pinfunction "2_2") (pintype "passive"))
      (node (ref "C66") (pin "2") (pinfunction "2_2") (pintype "passive"))
      (node (ref "C69") (pin "1") (pinfunction "1_1") (pintype "passive"))
      (node (ref "D15") (pin "2") (pinfunction "A_2") (pintype "passive"))
      (node (ref "Q12") (pin "2") (pinfunction "E_2") (pintype "passive"))
      (node (ref "R74") (pin "2") (pinfunction "2_2") (pintype "passive"))
      (node (ref "R82") (pin "1") (pinfunction "1_1") (pintype "passive"))
      (node (ref "R85") (pin "2") (pinfunction "2_2") (pintype "passive"))
      (node (ref "R87") (pin "2") (pinfunction "2_2") (pintype "passive"))
      (node (ref "TP12") (pin "1") (pintype "passive"))
      (node (ref "U8") (pin "2") (pinfunction "V-_2") (pintype "power_in"))
    )
    (net (code "28") (name "PWRGND12") (class "Default")
      (node (ref "C47") (pin "2") (pinfunction "2_2") (pintype "passive"))
      (node (ref "C48") (pin "2") (pinfunction "2_2") (pintype "passive"))
      (node (ref "C49") (pin "1") (pinfunction "+_1") (pintype "passive"))
      (node (ref "C53") (pin "1") (pinfunction "1_1") (pintype "passive"))
      (node (ref "C54") (pin "1") (pinfunction "1_1") (pintype "passive"))
      (node (ref "C55") (pin "2") (pinfunction "-_2") (pintype "passive"))
      (node (ref "J8") (pin "1") (pinfunction "1_1") (pintype "passive"))
      (node (ref "J9") (pin "2") (pinfunction "2_2") (pintype "passive"))
      (node (ref "R78") (pin "2") (pinfunction "2_2") (pintype "passive"))
      (node (ref "R82") (pin "2") (pinfunction "2_2") (pintype "passive"))
      (node (ref "T3") (pin "8") (pinfunction "8_8") (pintype "passive"))
    )
    (net (code "29") (name "VCONT2") (class "Default")
      (node (ref "R73") (pin "2") (pinfunction "2_2") (pintype "passive"))
      (node (ref "TP11") (pin "1") (pintype "passive"))
    )
    (net (code "30") (name "VOPAMP2") (class "Default")
      (node (ref "C58") (pin "1") (pinfunction "1_1") (pintype "passive"))
      (node (ref "C59") (pin "1") (pinfunction "1_1") (pintype "passive"))
      (node (ref "Q11") (pin "2") (pinfunction "E_2") (pintype "passive"))
      (node (ref "U8") (pin "5") (pinfunction "V+_5") (pintype "power_in"))
    )
    (net (code "31") (name "Vin") (class "Default")
      (node (ref "C44") (pin "1") (pinfunction "+_1") (pintype "passive"))
      (node (ref "C45") (pin "1") (pinfunction "1_1") (pintype "passive"))
      (node (ref "C46") (pin "1") (pinfunction "1_1") (pintype "passive"))
      (node (ref "C50") (pin "1") (pinfunction "1_1") (pintype "passive"))
      (node (ref "D13") (pin "1") (pinfunction "K_1") (pintype "passive"))
      (node (ref "Q11") (pin "3") (pinfunction "C_3") (pintype "passive"))
      (node (ref "R60") (pin "2") (pinfunction "2_2") (pintype "passive"))
      (node (ref "R61") (pin "2") (pinfunction "2_2") (pintype "passive"))
      (node (ref "R62") (pin "2") (pinfunction "2_2") (pintype "passive"))
      (node (ref "R63") (pin "1") (pinfunction "1_1") (pintype "passive"))
      (node (ref "R64") (pin "2") (pinfunction "2_2") (pintype "passive"))
      (node (ref "R80") (pin "2") (pinfunction "2_2") (pintype "passive"))
      (node (ref "T3") (pin "2") (pinfunction "2_2") (pintype "passive"))
    )
    (net (code "32") (name "unconnected-(T3-NC-Pad1)") (class "Default")
      (node (ref "T3") (pin "1") (pinfunction "NC_1") (pintype "passive"))
    )
    (net (code "33") (name "unconnected-(T3-NC-Pad3)") (class "Default")
      (node (ref "T3") (pin "3") (pinfunction "NC_3") (pintype "passive"))
    )
    (net (code "34") (name "unconnected-(T3-NC-Pad5)") (class "Default")
      (node (ref "T3") (pin "5") (pinfunction "NC_5") (pintype "passive"))
    )
    (net (code "35") (name "unconnected-(T3-NC-Pad6)") (class "Default")
      (node (ref "T3") (pin "6") (pinfunction "NC_6") (pintype "passive"))
    )
    (net (code "36") (name "unconnected-(T3-NC-Pad10)") (class "Default")
      (node (ref "T3") (pin "10") (pinfunction "NC_10") (pintype "passive"))
    )
  )
)
